# MonitoringProtection.net
KiCad netlist of a schematic drawn in Altium Designer
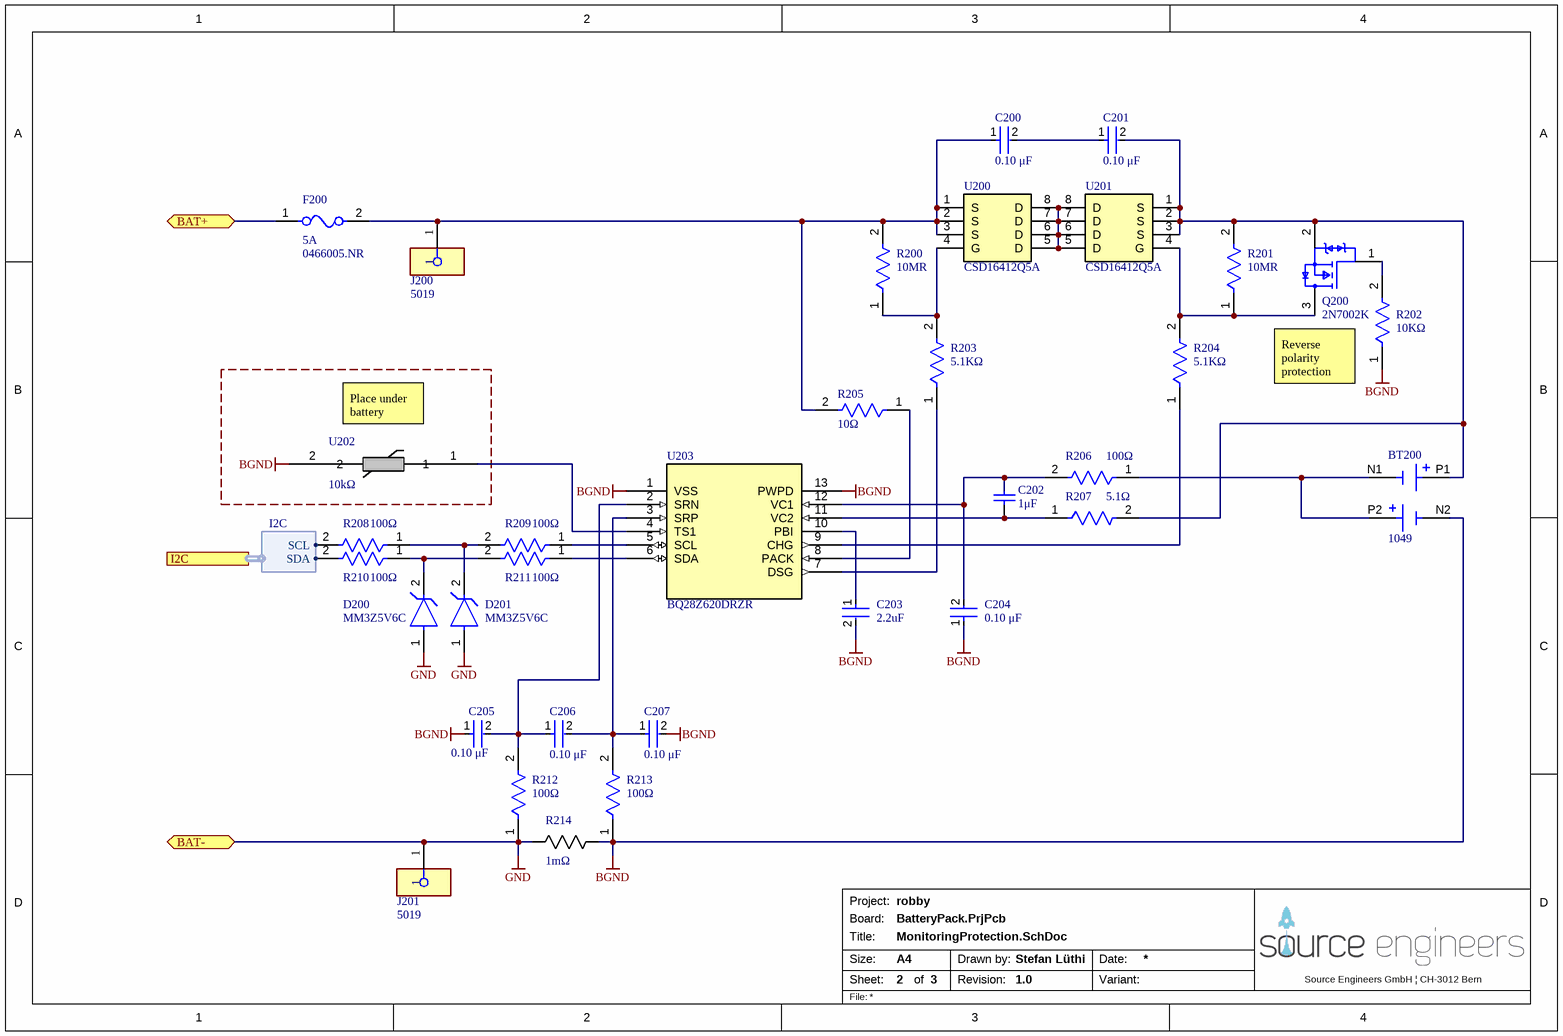
[diagram p0: MonitoringProtection.SchDoc]

(export (version "E")
  (design (tool "Eeschema 10.0.6"))
  (components
    (comp (ref "BT200")
      (value "1049")
      (footprint "BAT1049")
      (description "THM Holder for Dual 18650 Batteries")
      (fields (field (name "MF") "Keystone Electronics"))
      (libsource (lib "robby") (part "1049"))
    )
    (comp (ref "C200")
      (value "0.10 μF")
      (footprint "FP-C0603C-CF-MFG")
      (description "CAP CER 0.1UF 50V 20% X7R 0603")
      (fields
        (field (name "MANUFACTURER PART NUMBER") "C0603C104M5RACTU")
        (field (name "MANUFACTURER") "KEMET")
      )
      (libsource (lib "Altium Content Vault") (part "b4654b650e69147ec39a6b967a45e02"))
    )
    (comp (ref "C201")
      (value "0.10 μF")
      (footprint "FP-C0603C-CF-MFG")
      (description "CAP CER 0.1UF 50V 20% X7R 0603")
      (fields
        (field (name "MANUFACTURER PART NUMBER") "C0603C104M5RACTU")
        (field (name "MANUFACTURER") "KEMET")
      )
      (libsource (lib "Altium Content Vault") (part "b4654b650e69147ec39a6b967a45e02"))
    )
    (comp (ref "C202")
      (value "GRM219R71E105KA88D")
      (footprint "CAPC2013X95X45NL10T25")
      (fields (field (name "MANUFACTURER") "Murata") (field (name "PARAMETER 1") "1μF"))
      (libsource (lib "Altium Content Vault") (part "CAP"))
    )
    (comp (ref "C203")
      (value "GRM188R61E225KA12D")
      (footprint "FP-GRM188-0_1-e0_2_0_5-MFG")
      (description "Chip Multilayer Ceramic Capacitors for General Purpose, 0603, 2.2uF, X5R, 15%, 10%, 25V")
      (fields
        (field (name "TOLERANCE") "10%")
        (field (name "VOLTAGE") "25V")
        (field (name "CAPACITANCE") "2.2uF")
      )
      (libsource (lib "Altium Content Vault") (part "11868f565c42a9108669ba33697ecf6"))
    )
    (comp (ref "C204")
      (value "0.10 μF")
      (footprint "FP-C0603C-CF-MFG")
      (description "CAP CER 0.1UF 50V 20% X7R 0603")
      (fields
        (field (name "MANUFACTURER PART NUMBER") "C0603C104M5RACTU")
        (field (name "MANUFACTURER") "KEMET")
      )
      (libsource (lib "Altium Content Vault") (part "b4654b650e69147ec39a6b967a45e02"))
    )
    (comp (ref "C205")
      (value "0.10 μF")
      (footprint "FP-C0603C-CF-MFG")
      (description "CAP CER 0.1UF 50V 20% X7R 0603")
      (fields
        (field (name "MANUFACTURER PART NUMBER") "C0603C104M5RACTU")
        (field (name "MANUFACTURER") "KEMET")
      )
      (libsource (lib "Altium Content Vault") (part "b4654b650e69147ec39a6b967a45e02"))
    )
    (comp (ref "C206")
      (value "0.10 μF")
      (footprint "FP-C0603C-CF-MFG")
      (description "CAP CER 0.1UF 50V 20% X7R 0603")
      (fields
        (field (name "MANUFACTURER PART NUMBER") "C0603C104M5RACTU")
        (field (name "MANUFACTURER") "KEMET")
      )
      (libsource (lib "Altium Content Vault") (part "b4654b650e69147ec39a6b967a45e02"))
    )
    (comp (ref "C207")
      (value "0.10 μF")
      (footprint "FP-C0603C-CF-MFG")
      (description "CAP CER 0.1UF 50V 20% X7R 0603")
      (fields
        (field (name "MANUFACTURER PART NUMBER") "C0603C104M5RACTU")
        (field (name "MANUFACTURER") "KEMET")
      )
      (libsource (lib "Altium Content Vault") (part "b4654b650e69147ec39a6b967a45e02"))
    )
    (comp (ref "D200")
      (value "MM3Z5V6C")
      (footprint "FP-SOD-323F-MFG")
      (description "DIODE ZENER 5.6V 200MW SOD323F")
      (fields
        (field (name "MANUFACTURER") "ON Semiconductor")
        (field (name "OCTOPART") "https://octopart.com/mm3z5v6c-on+semiconductor-84329899")
      )
      (libsource (lib "Altium Content Vault") (part "3fba79ac723ca0a4e69928609483429"))
    )
    (comp (ref "D201")
      (value "MM3Z5V6C")
      (footprint "FP-SOD-323F-MFG")
      (description "DIODE ZENER 5.6V 200MW SOD323F")
      (fields
        (field (name "MANUFACTURER") "ON Semiconductor")
        (field (name "OCTOPART") "https://octopart.com/mm3z5v6c-on+semiconductor-84329899")
      )
      (libsource (lib "Altium Content Vault") (part "3fba79ac723ca0a4e69928609483429"))
    )
    (comp (ref "F200")
      (value "0466005.NR")
      (footprint "FP-0466-MFG")
      (description "FUSE BOARD MNT 5A 32VAC/VDC 1206")
      (fields
        (field (name "FUSE CURRENT") "5A")
        (field (name "OCTOPART") "https://octopart.com/0466005.nr-littelfuse-143206")
        (field (name "MANUFACTURER") "Littelfuse Inc")
      )
      (libsource (lib "Altium Content Vault") (part "5bcf9b9f640e542cf0359d10258e979"))
    )
    (comp (ref "J200")
      (value "5019")
      (footprint "FP-5019-MFG")
      (libsource (lib "Altium Content Vault") (part "98815daf2f2c152b0c43f5ab9800df6"))
    )
    (comp (ref "J201")
      (value "5019")
      (footprint "FP-5019-MFG")
      (libsource (lib "Altium Content Vault") (part "98815daf2f2c152b0c43f5ab9800df6"))
    )
    (comp (ref "Q200")
      (value "2N7002K")
      (footprint "FP-318-08-MFG")
      (description "MOSFET N-CH 60V 300MA SOT23")
      (fields
        (field (name "OCTOPART") "https://octopart.com/2n7002k-on+semiconductor-84408900")
        (field (name "MANUFACTURER") "ON Semiconductor")
      )
      (libsource (lib "Altium Content Vault") (part "40bafa8609a25cdbb0dab398ef4a0d9"))
    )
    (comp (ref "R200")
      (value "AC0603FR-0710ML")
      (footprint "FP-AC0603-IPC_C")
      (description "RES 10MΩ 1.00% 0.1W 0603")
      (fields (field (name "RESISTANCE") "10MR") (field (name "TOLERANCE") "1%"))
      (libsource (lib "Altium Content Vault") (part "1029c3af85768c4190bb7ad29bc67b5"))
    )
    (comp (ref "R201")
      (value "AC0603FR-0710ML")
      (footprint "FP-AC0603-IPC_C")
      (description "RES 10MΩ 1.00% 0.1W 0603")
      (fields (field (name "RESISTANCE") "10MR") (field (name "TOLERANCE") "1%"))
      (libsource (lib "Altium Content Vault") (part "1029c3af85768c4190bb7ad29bc67b5"))
    )
    (comp (ref "R202")
      (value "10KΩ")
      (footprint "FP-RT0603-MFG")
      (description "RES SMD 10K OHM 1% 1/10W 0603")
      (fields
        (field (name "MANUFACTURER") "Yageo")
        (field (name "OCTOPART") "https://octopart.com/rt0603fre0710kl-yageo-40009243")
      )
      (libsource (lib "Altium Content Vault") (part "1029c3af85768c4190bb7ad29bc67b5"))
    )
    (comp (ref "R203")
      (value "RT0603FRE075K1L")
      (footprint "FP-RT0603-MFG")
      (description "RES SMD 5.1K OHM 1% 1/10W 0603")
      (fields
        (field (name "RESISTANCE") "5.1KΩ")
        (field (name "MANUFACTURER") "Yageo")
        (field (name "OCTOPART") "https://octopart.com/rt0603fre075k1l-yageo-1421390")
      )
      (libsource (lib "Altium Content Vault") (part "1029c3af85768c4190bb7ad29bc67b5"))
    )
    (comp (ref "R204")
      (value "RT0603FRE075K1L")
      (footprint "FP-RT0603-MFG")
      (description "RES SMD 5.1K OHM 1% 1/10W 0603")
      (fields
        (field (name "RESISTANCE") "5.1KΩ")
        (field (name "MANUFACTURER") "Yageo")
        (field (name "OCTOPART") "https://octopart.com/rt0603fre075k1l-yageo-1421390")
      )
      (libsource (lib "Altium Content Vault") (part "1029c3af85768c4190bb7ad29bc67b5"))
    )
    (comp (ref "R205")
      (value "RT0603FRE0710RL")
      (footprint "FP-RT0603-MFG")
      (description "RES SMD 10 OHM 1% 1/10W 0603")
      (fields
        (field (name "MANUFACTURER") "Yageo")
        (field (name "RESISTANCE") "10Ω")
        (field (name "TOLERANCE") "0.01")
      )
      (libsource (lib "Altium Content Vault") (part "1029c3af85768c4190bb7ad29bc67b5"))
    )
    (comp (ref "R206")
      (value "RT0603FRE07100RL")
      (footprint "FP-RT0603-MFG")
      (description "RES SMD 100 OHM 1% 1/10W 0603")
      (fields
        (field (name "MANUFACTURER") "Yageo")
        (field (name "RESISTANCE") "100Ω")
        (field (name "TOLERANCE") "0.01")
      )
      (libsource (lib "Altium Content Vault") (part "1029c3af85768c4190bb7ad29bc67b5"))
    )
    (comp (ref "R207")
      (value "RT0603FRE075R1L")
      (footprint "FP-RT0603-MFG")
      (description "RES SMD 5.1 OHM 1% 1/10W 0603")
      (fields
        (field (name "OCTOPART") "https://octopart.com/rt0603fre075r1l-yageo-25630341")
        (field (name "MANUFACTURER") "Yageo")
        (field (name "RESISTANCE") "5.1Ω")
      )
      (libsource (lib "Altium Content Vault") (part "1029c3af85768c4190bb7ad29bc67b5"))
    )
    (comp (ref "R208")
      (value "RT0603FRE07100RL")
      (footprint "FP-RT0603-MFG")
      (description "RES SMD 100 OHM 1% 1/10W 0603")
      (fields
        (field (name "MANUFACTURER") "Yageo")
        (field (name "RESISTANCE") "100Ω")
        (field (name "TOLERANCE") "0.01")
      )
      (libsource (lib "Altium Content Vault") (part "1029c3af85768c4190bb7ad29bc67b5"))
    )
    (comp (ref "R209")
      (value "RT0603FRE07100RL")
      (footprint "FP-RT0603-MFG")
      (description "RES SMD 100 OHM 1% 1/10W 0603")
      (fields
        (field (name "MANUFACTURER") "Yageo")
        (field (name "RESISTANCE") "100Ω")
        (field (name "TOLERANCE") "0.01")
      )
      (libsource (lib "Altium Content Vault") (part "1029c3af85768c4190bb7ad29bc67b5"))
    )
    (comp (ref "R210")
      (value "RT0603FRE07100RL")
      (footprint "FP-RT0603-MFG")
      (description "RES SMD 100 OHM 1% 1/10W 0603")
      (fields
        (field (name "MANUFACTURER") "Yageo")
        (field (name "RESISTANCE") "100Ω")
        (field (name "TOLERANCE") "0.01")
      )
      (libsource (lib "Altium Content Vault") (part "1029c3af85768c4190bb7ad29bc67b5"))
    )
    (comp (ref "R211")
      (value "RT0603FRE07100RL")
      (footprint "FP-RT0603-MFG")
      (description "RES SMD 100 OHM 1% 1/10W 0603")
      (fields
        (field (name "MANUFACTURER") "Yageo")
        (field (name "RESISTANCE") "100Ω")
        (field (name "TOLERANCE") "0.01")
      )
      (libsource (lib "Altium Content Vault") (part "1029c3af85768c4190bb7ad29bc67b5"))
    )
    (comp (ref "R212")
      (value "RT0603FRE07100RL")
      (footprint "FP-RT0603-MFG")
      (description "RES SMD 100 OHM 1% 1/10W 0603")
      (fields
        (field (name "MANUFACTURER") "Yageo")
        (field (name "RESISTANCE") "100Ω")
        (field (name "TOLERANCE") "0.01")
      )
      (libsource (lib "Altium Content Vault") (part "1029c3af85768c4190bb7ad29bc67b5"))
    )
    (comp (ref "R213")
      (value "RT0603FRE07100RL")
      (footprint "FP-RT0603-MFG")
      (description "RES SMD 100 OHM 1% 1/10W 0603")
      (fields
        (field (name "MANUFACTURER") "Yageo")
        (field (name "RESISTANCE") "100Ω")
        (field (name "TOLERANCE") "0.01")
      )
      (libsource (lib "Altium Content Vault") (part "1029c3af85768c4190bb7ad29bc67b5"))
    )
    (comp (ref "R214")
      (value "CSNL1206FT1L00")
      (footprint "STA_CSNL1206_STP")
      (description "Description")
      (fields
        (field (name "PARAMETER 1") "1mΩ")
        (field (name "COPYRIGHT") "Copyright (C) 2025 Ultra Librarian. All rights reserved.")
      )
      (libsource (lib "robby") (part "CSNL1206FT1L00"))
    )
    (comp (ref "U200")
      (value "CSD16412Q5A")
      (footprint "DQJ8")
      (description "25-V, N channel NexFETâ„¢ power MOSFET, single SON 5 mm x 6 mm, 16 mOhm 8-VSONP -55 to 150")
      (fields (field (name "COPYRIGHT") "Copyright (C) 2025 Ultra Librarian. All rights reserved."))
      (libsource (lib "") (part "CSD16412Q5A_1"))
    )
    (comp (ref "U201")
      (value "CSD16412Q5A")
      (footprint "DQJ8")
      (description "25-V, N channel NexFETâ„¢ power MOSFET, single SON 5 mm x 6 mm, 16 mOhm 8-VSONP -55 to 150")
      (fields (field (name "COPYRIGHT") "Copyright (C) 2025 Ultra Librarian. All rights reserved."))
      (libsource (lib "robby") (part "CSD16412Q5A"))
    )
    (comp (ref "U202")
      (value "NTCS0603E3103FLT")
      (footprint "NTCS0603_VIS")
      (description "THERMISTOR NTC 10KOHM 3435K 0603")
      (fields (field (name "TOLERANCE") "1%") (field (name "RESISTANCE") "10kΩ"))
      (libsource (lib "Altium Content Vault") (part "NTCS0603E3103FLT"))
    )
    (comp (ref "U203")
      (value "BQ28Z620DRZR")
      (footprint "VSON12_DRZ_TEX")
      (fields (field (name "COPYRIGHT") "Copyright (C) 2025 Ultra Librarian. All rights reserved."))
      (libsource (lib "robby") (part "BQ28Z620DRZR"))
    )
  )
  (nets
    (net (code "2") (name "/BAT+") (class "Default")
      (node (ref "F200") (pin "1") (pinfunction "1_1") (pintype "passive"))
    )
    (net (code "3") (name "/SCL") (class "Default")
      (node (ref "R208") (pin "2") (pinfunction "2_2") (pintype "passive"))
    )
    (net (code "4") (name "/SDA") (class "Default")
      (node (ref "R210") (pin "2") (pinfunction "2_2") (pintype "passive"))
    )
    (net (code "6") (name "BGND") (class "Default")
      (node (ref "BT200") (pin "N2") (pinfunction "NEG2_N2") (pintype "passive"))
      (node (ref "C203") (pin "2") (pinfunction "2_2") (pintype "passive"))
      (node (ref "C204") (pin "1") (pinfunction "1_1") (pintype "passive"))
      (node (ref "C205") (pin "1") (pinfunction "1_1") (pintype "passive"))
      (node (ref "C207") (pin "2") (pinfunction "2_2") (pintype "passive"))
      (node (ref "R202") (pin "1") (pinfunction "1_1") (pintype "passive"))
      (node (ref "R213") (pin "1") (pinfunction "1_1") (pintype "passive"))
      (node (ref "R214") (pin "2") (pinfunction "2_2") (pintype "passive"))
      (node (ref "U202") (pin "2") (pinfunction "2_2") (pintype "passive"))
      (node (ref "U203") (pin "1") (pinfunction "VSS_1") (pintype "power_in"))
      (node (ref "U203") (pin "13") (pinfunction "PWPD_13") (pintype "power_in"))
    )
    (net (code "7") (name "GND") (class "Default")
      (node (ref "D200") (pin "1") (pinfunction "A_1") (pintype "passive"))
      (node (ref "D201") (pin "1") (pinfunction "A_1") (pintype "passive"))
      (node (ref "J201") (pin "1") (pinfunction "1_1") (pintype "passive"))
      (node (ref "R212") (pin "1") (pinfunction "1_1") (pintype "passive"))
      (node (ref "R214") (pin "1") (pinfunction "1_1") (pintype "passive"))
    )
    (net (code "8") (name "Net-(BT200-NEG1)") (class "Default")
      (node (ref "BT200") (pin "N1") (pinfunction "NEG1_N1") (pintype "passive"))
      (node (ref "BT200") (pin "P2") (pinfunction "POS2_P2") (pintype "passive"))
      (node (ref "R206") (pin "1") (pinfunction "1_1") (pintype "passive"))
    )
    (net (code "9") (name "Net-(BT200-POS1)") (class "Default")
      (node (ref "BT200") (pin "P1") (pinfunction "POS1_P1") (pintype "passive"))
      (node (ref "C201") (pin "2") (pinfunction "2_2") (pintype "passive"))
      (node (ref "Q200") (pin "2") (pinfunction "Source_2") (pintype "passive"))
      (node (ref "R201") (pin "2") (pinfunction "2_2") (pintype "passive"))
      (node (ref "R207") (pin "2") (pinfunction "2_2") (pintype "passive"))
      (node (ref "U201") (pin "1") (pinfunction "S_1") (pintype "passive"))
      (node (ref "U201") (pin "2") (pinfunction "S_2") (pintype "passive"))
      (node (ref "U201") (pin "3") (pinfunction "S_3") (pintype "passive"))
    )
    (net (code "10") (name "Net-(C200-Pad1)") (class "Default")
      (node (ref "C200") (pin "1") (pinfunction "1_1") (pintype "passive"))
      (node (ref "F200") (pin "2") (pinfunction "2_2") (pintype "passive"))
      (node (ref "J200") (pin "1") (pinfunction "1_1") (pintype "passive"))
      (node (ref "R200") (pin "2") (pinfunction "2_2") (pintype "passive"))
      (node (ref "R205") (pin "2") (pinfunction "2_2") (pintype "passive"))
      (node (ref "U200") (pin "1") (pinfunction "S_1") (pintype "passive"))
      (node (ref "U200") (pin "2") (pinfunction "S_2") (pintype "passive"))
      (node (ref "U200") (pin "3") (pinfunction "S_3") (pintype "passive"))
    )
    (net (code "11") (name "Net-(C200-Pad2)") (class "Default")
      (node (ref "C200") (pin "2") (pinfunction "2_2") (pintype "passive"))
      (node (ref "C201") (pin "1") (pinfunction "1_1") (pintype "passive"))
    )
    (net (code "12") (name "Net-(D200-C)") (class "Default")
      (node (ref "D200") (pin "2") (pinfunction "C_2") (pintype "passive"))
      (node (ref "R210") (pin "1") (pinfunction "1_1") (pintype "passive"))
      (node (ref "R211") (pin "2") (pinfunction "2_2") (pintype "passive"))
    )
    (net (code "13") (name "Net-(D201-C)") (class "Default")
      (node (ref "D201") (pin "2") (pinfunction "C_2") (pintype "passive"))
      (node (ref "R208") (pin "1") (pinfunction "1_1") (pintype "passive"))
      (node (ref "R209") (pin "2") (pinfunction "2_2") (pintype "passive"))
    )
    (net (code "14") (name "Net-(Q200-Drain)") (class "Default")
      (node (ref "Q200") (pin "3") (pinfunction "Drain_3") (pintype "passive"))
      (node (ref "R201") (pin "1") (pinfunction "1_1") (pintype "passive"))
      (node (ref "R204") (pin "2") (pinfunction "2_2") (pintype "passive"))
      (node (ref "U201") (pin "4") (pinfunction "G_4") (pintype "passive"))
    )
    (net (code "15") (name "Net-(Q200-Gate)") (class "Default")
      (node (ref "Q200") (pin "1") (pinfunction "Gate_1") (pintype "passive"))
      (node (ref "R202") (pin "2") (pinfunction "2_2") (pintype "passive"))
    )
    (net (code "16") (name "Net-(U200-D-Pad5)") (class "Default")
      (node (ref "U200") (pin "5") (pinfunction "D_5") (pintype "passive"))
      (node (ref "U200") (pin "6") (pinfunction "D_6") (pintype "passive"))
      (node (ref "U200") (pin "7") (pinfunction "D_7") (pintype "passive"))
      (node (ref "U200") (pin "8") (pinfunction "D_8") (pintype "passive"))
      (node (ref "U201") (pin "5") (pinfunction "D_5") (pintype "passive"))
      (node (ref "U201") (pin "6") (pinfunction "D_6") (pintype "passive"))
      (node (ref "U201") (pin "7") (pinfunction "D_7") (pintype "passive"))
      (node (ref "U201") (pin "8") (pinfunction "D_8") (pintype "passive"))
    )
    (net (code "17") (name "Net-(U200-G)") (class "Default")
      (node (ref "R200") (pin "1") (pinfunction "1_1") (pintype "passive"))
      (node (ref "R203") (pin "2") (pinfunction "2_2") (pintype "passive"))
      (node (ref "U200") (pin "4") (pinfunction "G_4") (pintype "passive"))
    )
    (net (code "18") (name "Net-(U203-CHG)") (class "Default")
      (node (ref "R204") (pin "1") (pinfunction "1_1") (pintype "passive"))
      (node (ref "U203") (pin "9") (pinfunction "CHG_9") (pintype "output"))
    )
    (net (code "19") (name "Net-(U203-DSG)") (class "Default")
      (node (ref "R203") (pin "1") (pinfunction "1_1") (pintype "passive"))
      (node (ref "U203") (pin "7") (pinfunction "DSG_7") (pintype "output"))
    )
    (net (code "20") (name "Net-(U203-PACK)") (class "Default")
      (node (ref "R205") (pin "1") (pinfunction "1_1") (pintype "passive"))
      (node (ref "U203") (pin "8") (pinfunction "PACK_8") (pintype "input"))
    )
    (net (code "21") (name "Net-(U203-PBI)") (class "Default")
      (node (ref "C203") (pin "1") (pinfunction "1_1") (pintype "passive"))
      (node (ref "U203") (pin "10") (pinfunction "PBI_10") (pintype "power_in"))
    )
    (net (code "22") (name "Net-(U203-SCL)") (class "Default")
      (node (ref "R209") (pin "1") (pinfunction "1_1") (pintype "passive"))
      (node (ref "U203") (pin "5") (pinfunction "SCL_5") (pintype "bidirectional"))
    )
    (net (code "23") (name "Net-(U203-SDA)") (class "Default")
      (node (ref "R211") (pin "1") (pinfunction "1_1") (pintype "passive"))
      (node (ref "U203") (pin "6") (pinfunction "SDA_6") (pintype "bidirectional"))
    )
    (net (code "24") (name "Net-(U203-SRN)") (class "Default")
      (node (ref "C205") (pin "2") (pinfunction "2_2") (pintype "passive"))
      (node (ref "C206") (pin "1") (pinfunction "1_1") (pintype "passive"))
      (node (ref "R212") (pin "2") (pinfunction "2_2") (pintype "passive"))
      (node (ref "U203") (pin "2") (pinfunction "SRN_2") (pintype "input"))
    )
    (net (code "25") (name "Net-(U203-SRP)") (class "Default")
      (node (ref "C206") (pin "2") (pinfunction "2_2") (pintype "passive"))
      (node (ref "C207") (pin "1") (pinfunction "1_1") (pintype "passive"))
      (node (ref "R213") (pin "2") (pinfunction "2_2") (pintype "passive"))
      (node (ref "U203") (pin "3") (pinfunction "SRP_3") (pintype "input"))
    )
    (net (code "26") (name "Net-(U203-TS1)") (class "Default")
      (node (ref "U202") (pin "1") (pinfunction "1_1") (pintype "passive"))
      (node (ref "U203") (pin "4") (pinfunction "TS1_4") (pintype "input"))
    )
    (net (code "27") (name "Net-(U203-VC1)") (class "Default")
      (node (ref "C202") (pin "2") (pinfunction "2_2") (pintype "passive"))
      (node (ref "C204") (pin "2") (pinfunction "2_2") (pintype "passive"))
      (node (ref "R206") (pin "2") (pinfunction "2_2") (pintype "passive"))
      (node (ref "U203") (pin "12") (pinfunction "VC1_12") (pintype "input"))
    )
    (net (code "28") (name "Net-(U203-VC2)") (class "Default")
      (node (ref "C202") (pin "1") (pinfunction "1_1") (pintype "passive"))
      (node (ref "R207") (pin "1") (pinfunction "1_1") (pintype "passive"))
      (node (ref "U203") (pin "11") (pinfunction "VC2_11") (pintype "input"))
    )
  )
)
